# Autonoom.net
KiCad netlist of a schematic drawn in Altium Designer
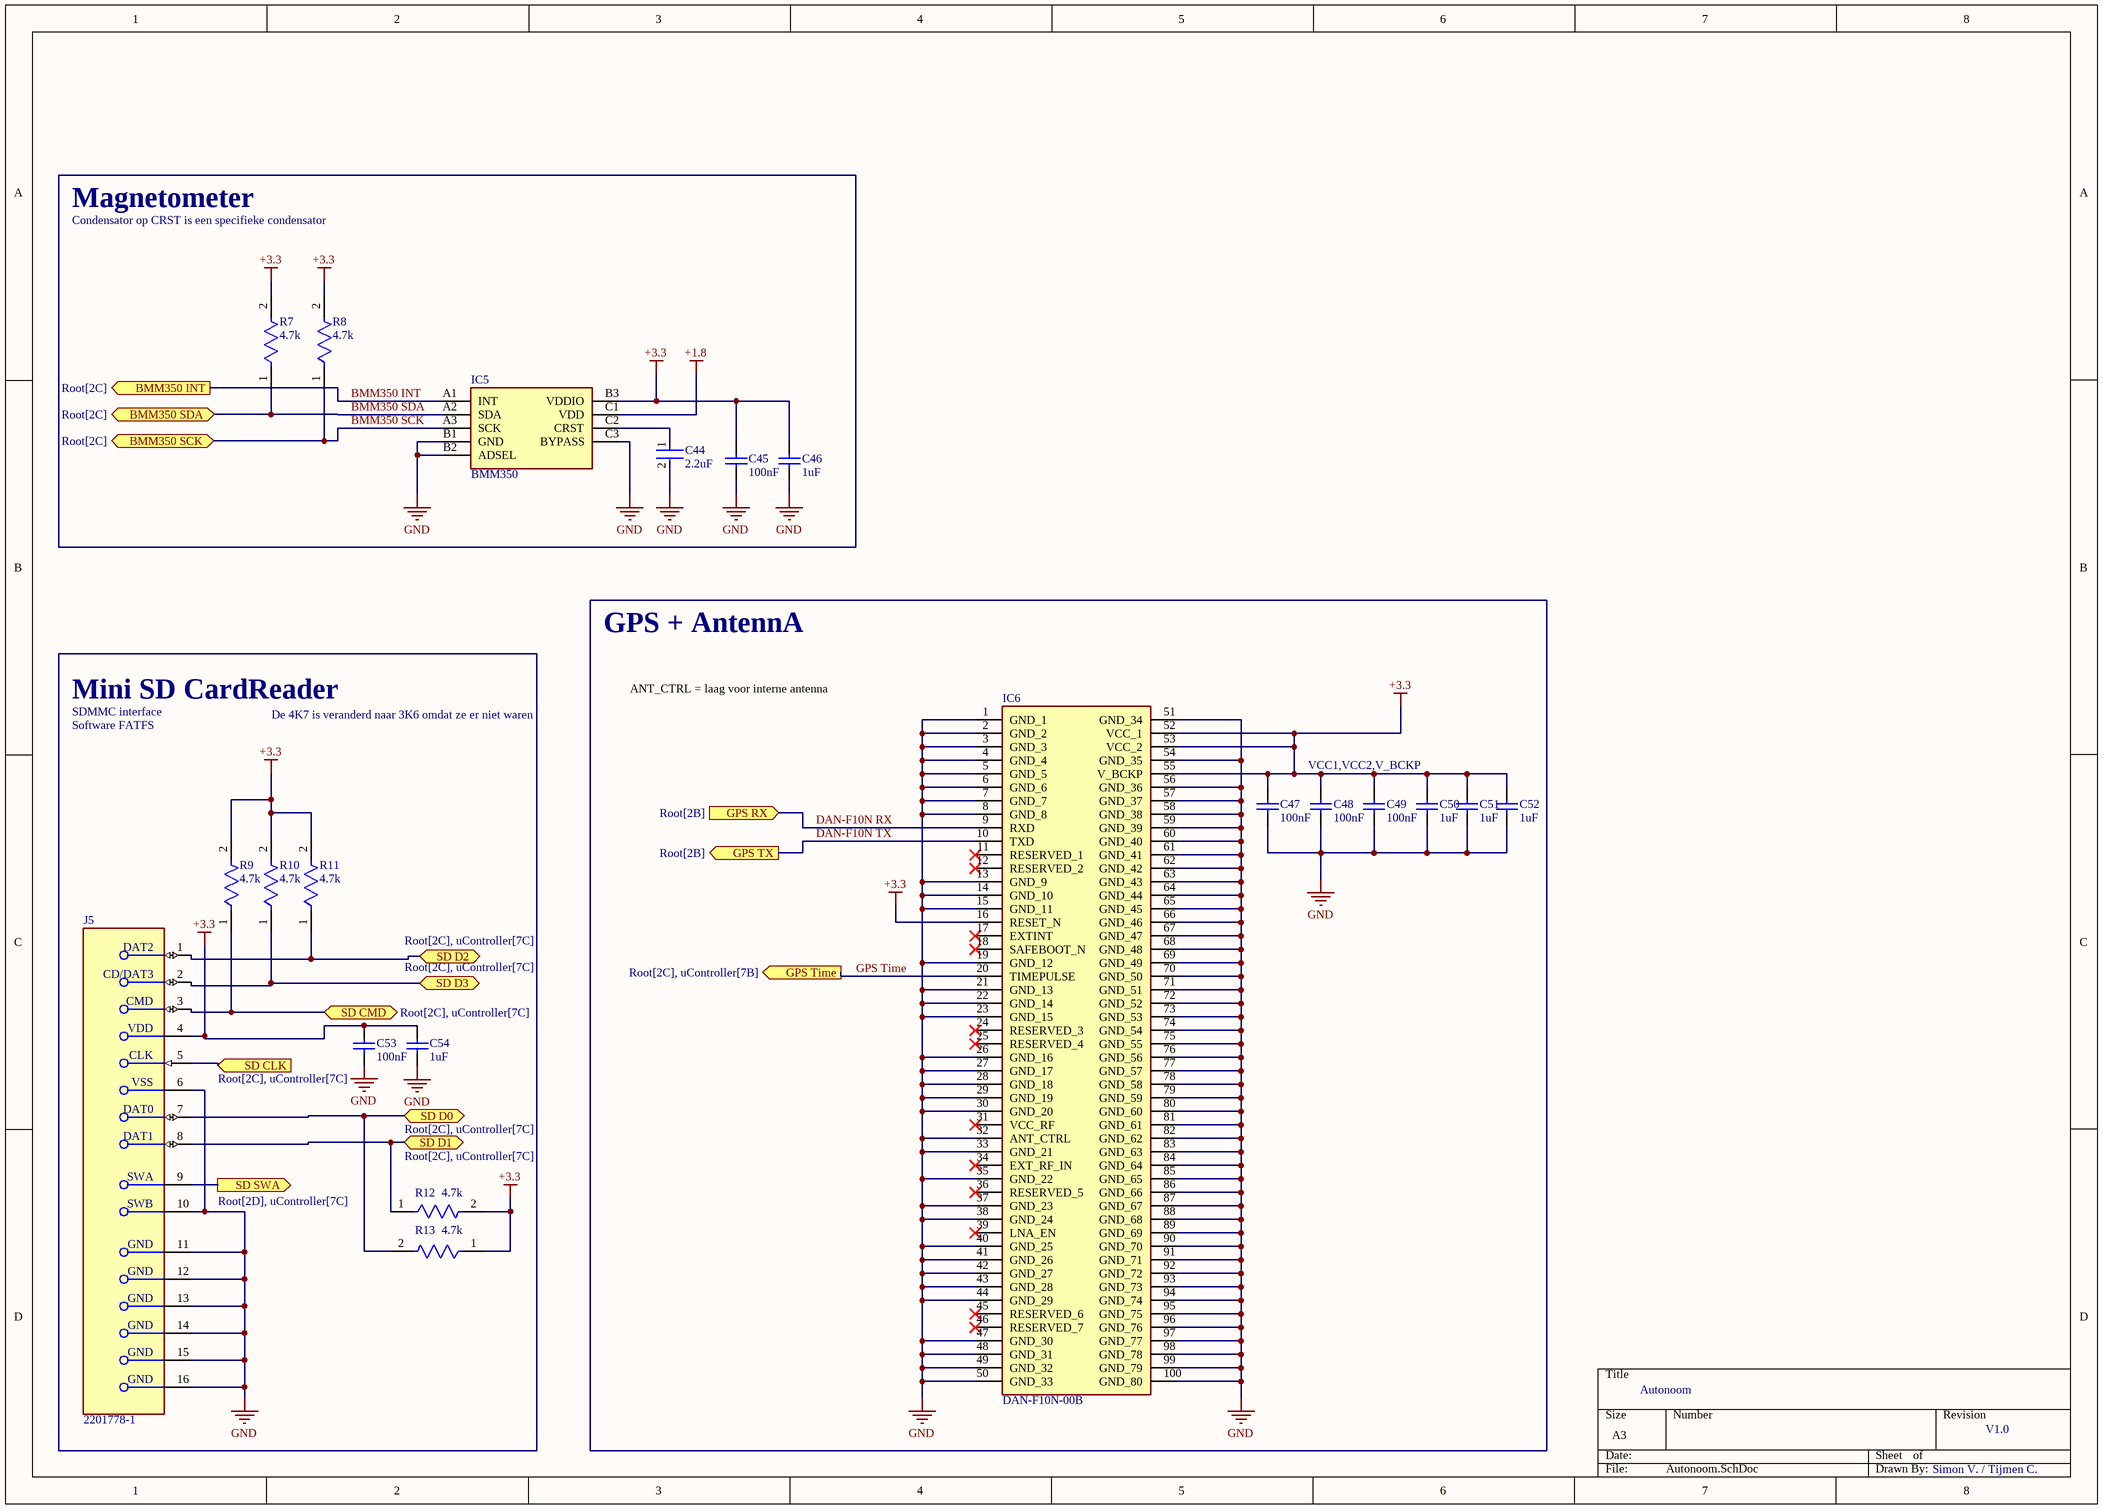
[diagram p0: Autonoom.SchDoc]

(export (version "E")
  (design (tool "Eeschema 10.0.6"))
  (components
    (comp (ref "C44")
      (value "2.2uF")
      (footprint "FP-CGB4B-MFG")
      (description "Multilayer Ceramic Capacitors 2.2uF ±10% 6.3V X7R SMD 0805, type: CGB4B3X7R0J225K055AB")
      (fields (field (name "TOLERANCE") "10%"))
      (libsource (lib "Altium Content Vault") (part "b4654b650e69147ec39a6b967a45e02"))
    )
    (comp (ref "C45")
      (value "100nF")
      (footprint "CAPC1608X92X38ML15T08")
      (fields (field (name "PART NUMBER") "VJ0603Y104MXXAC") (field (name "MANUFACTURER") "Vitramon"))
      (libsource (lib "Altium Content Vault") (part "CAP"))
    )
    (comp (ref "C46")
      (value "1uF")
      (footprint "CAPC1608X90X35NL15T15")
      (fields
        (field (name "PART NUMBER") "0603YD105MAT2A")
        (field (name "MANUFACTURER") "AVX Interconnect / Elco")
      )
      (libsource (lib "Altium Content Vault") (part "CAP"))
    )
    (comp (ref "C47")
      (value "100nF")
      (footprint "CAPC1608X92X38ML15T08")
      (fields (field (name "PART NUMBER") "VJ0603Y104MXXAC") (field (name "MANUFACTURER") "Vitramon"))
      (libsource (lib "Altium Content Vault") (part "CAP"))
    )
    (comp (ref "C48")
      (value "100nF")
      (footprint "CAPC1608X92X38ML15T08")
      (fields (field (name "PART NUMBER") "VJ0603Y104MXXAC") (field (name "MANUFACTURER") "Vitramon"))
      (libsource (lib "Altium Content Vault") (part "CAP"))
    )
    (comp (ref "C49")
      (value "100nF")
      (footprint "CAPC1608X92X38ML15T08")
      (fields (field (name "PART NUMBER") "VJ0603Y104MXXAC") (field (name "MANUFACTURER") "Vitramon"))
      (libsource (lib "Altium Content Vault") (part "CAP"))
    )
    (comp (ref "C50")
      (value "1uF")
      (footprint "CAPC1608X90X35NL15T15")
      (fields
        (field (name "PART NUMBER") "0603YD105MAT2A")
        (field (name "MANUFACTURER") "AVX Interconnect / Elco")
      )
      (libsource (lib "Altium Content Vault") (part "CAP"))
    )
    (comp (ref "C51")
      (value "1uF")
      (footprint "CAPC1608X90X35NL15T15")
      (fields
        (field (name "PART NUMBER") "0603YD105MAT2A")
        (field (name "MANUFACTURER") "AVX Interconnect / Elco")
      )
      (libsource (lib "Altium Content Vault") (part "CAP"))
    )
    (comp (ref "C52")
      (value "1uF")
      (footprint "CAPC1608X90X35NL15T15")
      (fields
        (field (name "PART NUMBER") "0603YD105MAT2A")
        (field (name "MANUFACTURER") "AVX Interconnect / Elco")
      )
      (libsource (lib "Altium Content Vault") (part "CAP"))
    )
    (comp (ref "C53")
      (value "100nF")
      (footprint "CAPC1608X92X38ML15T08")
      (fields (field (name "PART NUMBER") "VJ0603Y104MXXAC") (field (name "MANUFACTURER") "Vitramon"))
      (libsource (lib "Altium Content Vault") (part "CAP"))
    )
    (comp (ref "C54")
      (value "1uF")
      (footprint "CAPC1608X90X35NL15T15")
      (fields
        (field (name "PART NUMBER") "0603YD105MAT2A")
        (field (name "MANUFACTURER") "AVX Interconnect / Elco")
      )
      (libsource (lib "Altium Content Vault") (part "CAP"))
    )
    (comp (ref "IC5")
      (value "BMM350")
      (footprint "SamacSys:BGA9C40P3X3_128X128X54")
      (description "Integrated Circuit")
      (fields (field (name "MOUSER PART NUMBER") "262-BMM350"))
      (libsource (lib "SamacSys") (part "BMM350"))
    )
    (comp (ref "IC6")
      (value "DAN-F10N-00B")
      (footprint "SamacSys:DANF10N00B")
      (description "Integrated Circuit")
      (libsource (lib "*") (part "DAN-F10N-00B"))
    )
    (comp (ref "J5")
      (value "2201778-1")
      (footprint "FP-2201778-1-MFG")
      (description "MICRO SD PUSH PUSH LOW PROFILE T")
      (fields
        (field (name "OCTOPART") "https://octopart.com/2201778-1-te+connectivity-46448999")
        (field (name "MANUFACTURER") "TE Connectivity")
      )
      (libsource (lib "Altium Content Vault") (part "5f630df3b5079420789607a76de83c1"))
    )
    (comp (ref "R7")
      (value "4.7k")
      (footprint "FP-AC0603-IPC_A")
      (description "RES 4.7KΩ 1.00% 0.1W 0603")
      (fields (field (name "TOLERANCE") "1%"))
      (libsource (lib "Altium Content Vault") (part "1029c3af85768c4190bb7ad29bc67b5"))
    )
    (comp (ref "R8")
      (value "4.7k")
      (footprint "FP-AC0603-IPC_A")
      (description "RES 4.7KΩ 1.00% 0.1W 0603")
      (fields (field (name "TOLERANCE") "1%"))
      (libsource (lib "Altium Content Vault") (part "1029c3af85768c4190bb7ad29bc67b5"))
    )
    (comp (ref "R9")
      (value "4.7k")
      (footprint "FP-AC0603-IPC_A")
      (description "RES 4.7KΩ 1.00% 0.1W 0603")
      (fields (field (name "TOLERANCE") "1%"))
      (libsource (lib "Altium Content Vault") (part "1029c3af85768c4190bb7ad29bc67b5"))
    )
    (comp (ref "R10")
      (value "4.7k")
      (footprint "FP-AC0603-IPC_A")
      (description "RES 4.7KΩ 1.00% 0.1W 0603")
      (fields (field (name "TOLERANCE") "1%"))
      (libsource (lib "Altium Content Vault") (part "1029c3af85768c4190bb7ad29bc67b5"))
    )
    (comp (ref "R11")
      (value "4.7k")
      (footprint "FP-AC0603-IPC_A")
      (description "RES 4.7KΩ 1.00% 0.1W 0603")
      (fields (field (name "TOLERANCE") "1%"))
      (libsource (lib "Altium Content Vault") (part "1029c3af85768c4190bb7ad29bc67b5"))
    )
    (comp (ref "R12")
      (value "4.7k")
      (footprint "FP-AC0603-IPC_A")
      (description "RES 4.7KΩ 1.00% 0.1W 0603")
      (fields (field (name "TOLERANCE") "1%"))
      (libsource (lib "Altium Content Vault") (part "1029c3af85768c4190bb7ad29bc67b5"))
    )
    (comp (ref "R13")
      (value "4.7k")
      (footprint "FP-AC0603-IPC_A")
      (description "RES 4.7KΩ 1.00% 0.1W 0603")
      (fields (field (name "TOLERANCE") "1%"))
      (libsource (lib "Altium Content Vault") (part "1029c3af85768c4190bb7ad29bc67b5"))
    )
  )
  (nets
    (net (code "1") (name "+1.8") (class "Default")
      (node (ref "IC5") (pin "C1") (pinfunction "VDD_C1") (pintype "passive"))
    )
    (net (code "2") (name "+3.3") (class "Default")
      (node (ref "C45") (pin "2") (pinfunction "2_2") (pintype "passive"))
      (node (ref "C46") (pin "2") (pinfunction "2_2") (pintype "passive"))
      (node (ref "C47") (pin "2") (pinfunction "2_2") (pintype "passive"))
      (node (ref "C48") (pin "2") (pinfunction "2_2") (pintype "passive"))
      (node (ref "C49") (pin "2") (pinfunction "2_2") (pintype "passive"))
      (node (ref "C50") (pin "2") (pinfunction "2_2") (pintype "passive"))
      (node (ref "C51") (pin "2") (pinfunction "2_2") (pintype "passive"))
      (node (ref "C52") (pin "2") (pinfunction "2_2") (pintype "passive"))
      (node (ref "C53") (pin "2") (pinfunction "2_2") (pintype "passive"))
      (node (ref "C54") (pin "2") (pinfunction "2_2") (pintype "passive"))
      (node (ref "IC5") (pin "B3") (pinfunction "VDDIO_B3") (pintype "passive"))
      (node (ref "IC6") (pin "16") (pinfunction "RESET_N_16") (pintype "passive"))
      (node (ref "IC6") (pin "52") (pinfunction "VCC_1_52") (pintype "passive"))
      (node (ref "IC6") (pin "53") (pinfunction "VCC_2_53") (pintype "passive"))
      (node (ref "IC6") (pin "55") (pinfunction "V_BCKP_55") (pintype "passive"))
      (node (ref "J5") (pin "4") (pinfunction "VDD_4") (pintype "power_in"))
      (node (ref "R10") (pin "2") (pinfunction "2_2") (pintype "passive"))
      (node (ref "R11") (pin "2") (pinfunction "2_2") (pintype "passive"))
      (node (ref "R12") (pin "2") (pinfunction "2_2") (pintype "passive"))
      (node (ref "R13") (pin "1") (pinfunction "1_1") (pintype "passive"))
      (node (ref "R7") (pin "2") (pinfunction "2_2") (pintype "passive"))
      (node (ref "R8") (pin "2") (pinfunction "2_2") (pintype "passive"))
      (node (ref "R9") (pin "2") (pinfunction "2_2") (pintype "passive"))
    )
    (net (code "3") (name "/BMM350 INT") (class "Default")
      (node (ref "IC5") (pin "A1") (pinfunction "INT_A1") (pintype "passive"))
    )
    (net (code "4") (name "/BMM350 SCK") (class "Default")
      (node (ref "IC5") (pin "A3") (pinfunction "SCK_A3") (pintype "passive"))
      (node (ref "R8") (pin "1") (pinfunction "1_1") (pintype "passive"))
    )
    (net (code "5") (name "/BMM350 SDA") (class "Default")
      (node (ref "IC5") (pin "A2") (pinfunction "SDA_A2") (pintype "passive"))
      (node (ref "R7") (pin "1") (pinfunction "1_1") (pintype "passive"))
    )
    (net (code "6") (name "/DAN-F10N RX") (class "Default")
      (node (ref "IC6") (pin "9") (pinfunction "RXD_9") (pintype "passive"))
    )
    (net (code "7") (name "/DAN-F10N TX") (class "Default")
      (node (ref "IC6") (pin "10") (pinfunction "TXD_10") (pintype "passive"))
    )
    (net (code "8") (name "/GPS Time") (class "Default")
      (node (ref "IC6") (pin "20") (pinfunction "TIMEPULSE_20") (pintype "passive"))
    )
    (net (code "9") (name "/SD CLK") (class "Default")
      (node (ref "J5") (pin "5") (pinfunction "CLK_5") (pintype "input"))
    )
    (net (code "10") (name "/SD CMD") (class "Default")
      (node (ref "J5") (pin "3") (pinfunction "CMD_3") (pintype "bidirectional"))
      (node (ref "R9") (pin "1") (pinfunction "1_1") (pintype "passive"))
    )
    (net (code "11") (name "/SD D0") (class "Default")
      (node (ref "J5") (pin "7") (pinfunction "DAT0_7") (pintype "bidirectional"))
      (node (ref "R13") (pin "2") (pinfunction "2_2") (pintype "passive"))
    )
    (net (code "12") (name "/SD D1") (class "Default")
      (node (ref "J5") (pin "8") (pinfunction "DAT1_8") (pintype "bidirectional"))
      (node (ref "R12") (pin "1") (pinfunction "1_1") (pintype "passive"))
    )
    (net (code "13") (name "/SD D2") (class "Default")
      (node (ref "J5") (pin "1") (pinfunction "DAT2_1") (pintype "bidirectional"))
      (node (ref "R11") (pin "1") (pinfunction "1_1") (pintype "passive"))
    )
    (net (code "14") (name "/SD D3") (class "Default")
      (node (ref "J5") (pin "2") (pinfunction "CD/DAT3_2") (pintype "bidirectional"))
      (node (ref "R10") (pin "1") (pinfunction "1_1") (pintype "passive"))
    )
    (net (code "15") (name "/SD SWA") (class "Default")
      (node (ref "J5") (pin "9") (pinfunction "SWA_9") (pintype "passive"))
    )
    (net (code "16") (name "GND") (class "Default")
      (node (ref "C44") (pin "2") (pinfunction "2_2") (pintype "passive"))
      (node (ref "C45") (pin "1") (pinfunction "1_1") (pintype "passive"))
      (node (ref "C46") (pin "1") (pinfunction "1_1") (pintype "passive"))
      (node (ref "C47") (pin "1") (pinfunction "1_1") (pintype "passive"))
      (node (ref "C48") (pin "1") (pinfunction "1_1") (pintype "passive"))
      (node (ref "C49") (pin "1") (pinfunction "1_1") (pintype "passive"))
      (node (ref "C50") (pin "1") (pinfunction "1_1") (pintype "passive"))
      (node (ref "C51") (pin "1") (pinfunction "1_1") (pintype "passive"))
      (node (ref "C52") (pin "1") (pinfunction "1_1") (pintype "passive"))
      (node (ref "C53") (pin "1") (pinfunction "1_1") (pintype "passive"))
      (node (ref "C54") (pin "1") (pinfunction "1_1") (pintype "passive"))
      (node (ref "IC5") (pin "B1") (pinfunction "GND_B1") (pintype "passive"))
      (node (ref "IC5") (pin "B2") (pinfunction "ADSEL_B2") (pintype "passive"))
      (node (ref "IC5") (pin "C3") (pinfunction "BYPASS_C3") (pintype "passive"))
      (node (ref "IC6") (pin "1") (pinfunction "GND_1_1") (pintype "passive"))
      (node (ref "IC6") (pin "100") (pinfunction "GND_80_100") (pintype "passive"))
      (node (ref "IC6") (pin "13") (pinfunction "GND_9_13") (pintype "passive"))
      (node (ref "IC6") (pin "14") (pinfunction "GND_10_14") (pintype "passive"))
      (node (ref "IC6") (pin "15") (pinfunction "GND_11_15") (pintype "passive"))
      (node (ref "IC6") (pin "19") (pinfunction "GND_12_19") (pintype "passive"))
      (node (ref "IC6") (pin "2") (pinfunction "GND_2_2") (pintype "passive"))
      (node (ref "IC6") (pin "21") (pinfunction "GND_13_21") (pintype "passive"))
      (node (ref "IC6") (pin "22") (pinfunction "GND_14_22") (pintype "passive"))
      (node (ref "IC6") (pin "23") (pinfunction "GND_15_23") (pintype "passive"))
      (node (ref "IC6") (pin "26") (pinfunction "GND_16_26") (pintype "passive"))
      (node (ref "IC6") (pin "27") (pinfunction "GND_17_27") (pintype "passive"))
      (node (ref "IC6") (pin "28") (pinfunction "GND_18_28") (pintype "passive"))
      (node (ref "IC6") (pin "29") (pinfunction "GND_19_29") (pintype "passive"))
      (node (ref "IC6") (pin "3") (pinfunction "GND_3_3") (pintype "passive"))
      (node (ref "IC6") (pin "30") (pinfunction "GND_20_30") (pintype "passive"))
      (node (ref "IC6") (pin "32") (pinfunction "ANT_CTRL_32") (pintype "passive"))
      (node (ref "IC6") (pin "33") (pinfunction "GND_21_33") (pintype "passive"))
      (node (ref "IC6") (pin "35") (pinfunction "GND_22_35") (pintype "passive"))
      (node (ref "IC6") (pin "37") (pinfunction "GND_23_37") (pintype "passive"))
      (node (ref "IC6") (pin "38") (pinfunction "GND_24_38") (pintype "passive"))
      (node (ref "IC6") (pin "4") (pinfunction "GND_4_4") (pintype "passive"))
      (node (ref "IC6") (pin "40") (pinfunction "GND_25_40") (pintype "passive"))
      (node (ref "IC6") (pin "41") (pinfunction "GND_26_41") (pintype "passive"))
      (node (ref "IC6") (pin "42") (pinfunction "GND_27_42") (pintype "passive"))
      (node (ref "IC6") (pin "43") (pinfunction "GND_28_43") (pintype "passive"))
      (node (ref "IC6") (pin "44") (pinfunction "GND_29_44") (pintype "passive"))
      (node (ref "IC6") (pin "47") (pinfunction "GND_30_47") (pintype "passive"))
      (node (ref "IC6") (pin "48") (pinfunction "GND_31_48") (pintype "passive"))
      (node (ref "IC6") (pin "49") (pinfunction "GND_32_49") (pintype "passive"))
      (node (ref "IC6") (pin "5") (pinfunction "GND_5_5") (pintype "passive"))
      (node (ref "IC6") (pin "50") (pinfunction "GND_33_50") (pintype "passive"))
      (node (ref "IC6") (pin "51") (pinfunction "GND_34_51") (pintype "passive"))
      (node (ref "IC6") (pin "54") (pinfunction "GND_35_54") (pintype "passive"))
      (node (ref "IC6") (pin "56") (pinfunction "GND_36_56") (pintype "passive"))
      (node (ref "IC6") (pin "57") (pinfunction "GND_37_57") (pintype "passive"))
      (node (ref "IC6") (pin "58") (pinfunction "GND_38_58") (pintype "passive"))
      (node (ref "IC6") (pin "59") (pinfunction "GND_39_59") (pintype "passive"))
      (node (ref "IC6") (pin "6") (pinfunction "GND_6_6") (pintype "passive"))
      (node (ref "IC6") (pin "60") (pinfunction "GND_40_60") (pintype "passive"))
      (node (ref "IC6") (pin "61") (pinfunction "GND_41_61") (pintype "passive"))
      (node (ref "IC6") (pin "62") (pinfunction "GND_42_62") (pintype "passive"))
      (node (ref "IC6") (pin "63") (pinfunction "GND_43_63") (pintype "passive"))
      (node (ref "IC6") (pin "64") (pinfunction "GND_44_64") (pintype "passive"))
      (node (ref "IC6") (pin "65") (pinfunction "GND_45_65") (pintype "passive"))
      (node (ref "IC6") (pin "66") (pinfunction "GND_46_66") (pintype "passive"))
      (node (ref "IC6") (pin "67") (pinfunction "GND_47_67") (pintype "passive"))
      (node (ref "IC6") (pin "68") (pinfunction "GND_48_68") (pintype "passive"))
      (node (ref "IC6") (pin "69") (pinfunction "GND_49_69") (pintype "passive"))
      (node (ref "IC6") (pin "7") (pinfunction "GND_7_7") (pintype "passive"))
      (node (ref "IC6") (pin "70") (pinfunction "GND_50_70") (pintype "passive"))
      (node (ref "IC6") (pin "71") (pinfunction "GND_51_71") (pintype "passive"))
      (node (ref "IC6") (pin "72") (pinfunction "GND_52_72") (pintype "passive"))
      (node (ref "IC6") (pin "73") (pinfunction "GND_53_73") (pintype "passive"))
      (node (ref "IC6") (pin "74") (pinfunction "GND_54_74") (pintype "passive"))
      (node (ref "IC6") (pin "75") (pinfunction "GND_55_75") (pintype "passive"))
      (node (ref "IC6") (pin "76") (pinfunction "GND_56_76") (pintype "passive"))
      (node (ref "IC6") (pin "77") (pinfunction "GND_57_77") (pintype "passive"))
      (node (ref "IC6") (pin "78") (pinfunction "GND_58_78") (pintype "passive"))
      (node (ref "IC6") (pin "79") (pinfunction "GND_59_79") (pintype "passive"))
      (node (ref "IC6") (pin "8") (pinfunction "GND_8_8") (pintype "passive"))
      (node (ref "IC6") (pin "80") (pinfunction "GND_60_80") (pintype "passive"))
      (node (ref "IC6") (pin "81") (pinfunction "GND_61_81") (pintype "passive"))
      (node (ref "IC6") (pin "82") (pinfunction "GND_62_82") (pintype "passive"))
      (node (ref "IC6") (pin "83") (pinfunction "GND_63_83") (pintype "passive"))
      (node (ref "IC6") (pin "84") (pinfunction "GND_64_84") (pintype "passive"))
      (node (ref "IC6") (pin "85") (pinfunction "GND_65_85") (pintype "passive"))
      (node (ref "IC6") (pin "86") (pinfunction "GND_66_86") (pintype "passive"))
      (node (ref "IC6") (pin "87") (pinfunction "GND_67_87") (pintype "passive"))
      (node (ref "IC6") (pin "88") (pinfunction "GND_68_88") (pintype "passive"))
      (node (ref "IC6") (pin "89") (pinfunction "GND_69_89") (pintype "passive"))
      (node (ref "IC6") (pin "90") (pinfunction "GND_70_90") (pintype "passive"))
      (node (ref "IC6") (pin "91") (pinfunction "GND_71_91") (pintype "passive"))
      (node (ref "IC6") (pin "92") (pinfunction "GND_72_92") (pintype "passive"))
      (node (ref "IC6") (pin "93") (pinfunction "GND_73_93") (pintype "passive"))
      (node (ref "IC6") (pin "94") (pinfunction "GND_74_94") (pintype "passive"))
      (node (ref "IC6") (pin "95") (pinfunction "GND_75_95") (pintype "passive"))
      (node (ref "IC6") (pin "96") (pinfunction "GND_76_96") (pintype "passive"))
      (node (ref "IC6") (pin "97") (pinfunction "GND_77_97") (pintype "passive"))
      (node (ref "IC6") (pin "98") (pinfunction "GND_78_98") (pintype "passive"))
      (node (ref "IC6") (pin "99") (pinfunction "GND_79_99") (pintype "passive"))
      (node (ref "J5") (pin "10") (pinfunction "SWB_10") (pintype "passive"))
      (node (ref "J5") (pin "11") (pinfunction "GND_11") (pintype "power_in"))
      (node (ref "J5") (pin "12") (pinfunction "GND_12") (pintype "power_in"))
      (node (ref "J5") (pin "13") (pinfunction "GND_13") (pintype "power_in"))
      (node (ref "J5") (pin "14") (pinfunction "GND_14") (pintype "power_in"))
      (node (ref "J5") (pin "15") (pinfunction "GND_15") (pintype "power_in"))
      (node (ref "J5") (pin "16") (pinfunction "GND_16") (pintype "power_in"))
      (node (ref "J5") (pin "6") (pinfunction "VSS_6") (pintype "power_in"))
    )
    (net (code "17") (name "Net-(IC5-CRST)") (class "Default")
      (node (ref "C44") (pin "1") (pinfunction "1_1") (pintype "passive"))
      (node (ref "IC5") (pin "C2") (pinfunction "CRST_C2") (pintype "passive"))
    )
    (net (code "18") (name "unconnected-(IC6-EXTINT-Pad17)") (class "Default")
      (node (ref "IC6") (pin "17") (pinfunction "EXTINT_17") (pintype "passive+no_connect"))
    )
    (net (code "19") (name "unconnected-(IC6-EXT_RF_IN-Pad34)") (class "Default")
      (node (ref "IC6") (pin "34") (pinfunction "EXT_RF_IN_34") (pintype "passive+no_connect"))
    )
    (net (code "20") (name "unconnected-(IC6-LNA_EN-Pad39)") (class "Default")
      (node (ref "IC6") (pin "39") (pinfunction "LNA_EN_39") (pintype "passive+no_connect"))
    )
    (net (code "21") (name "unconnected-(IC6-RESERVED_1-Pad11)") (class "Default")
      (node (ref "IC6") (pin "11") (pinfunction "RESERVED_1_11") (pintype "passive+no_connect"))
    )
    (net (code "22") (name "unconnected-(IC6-RESERVED_2-Pad12)") (class "Default")
      (node (ref "IC6") (pin "12") (pinfunction "RESERVED_2_12") (pintype "passive+no_connect"))
    )
    (net (code "23") (name "unconnected-(IC6-RESERVED_3-Pad24)") (class "Default")
      (node (ref "IC6") (pin "24") (pinfunction "RESERVED_3_24") (pintype "passive+no_connect"))
    )
    (net (code "24") (name "unconnected-(IC6-RESERVED_4-Pad25)") (class "Default")
      (node (ref "IC6") (pin "25") (pinfunction "RESERVED_4_25") (pintype "passive+no_connect"))
    )
    (net (code "25") (name "unconnected-(IC6-RESERVED_5-Pad36)") (class "Default")
      (node (ref "IC6") (pin "36") (pinfunction "RESERVED_5_36") (pintype "passive+no_connect"))
    )
    (net (code "26") (name "unconnected-(IC6-RESERVED_6-Pad45)") (class "Default")
      (node (ref "IC6") (pin "45") (pinfunction "RESERVED_6_45") (pintype "passive+no_connect"))
    )
    (net (code "27") (name "unconnected-(IC6-RESERVED_7-Pad46)") (class "Default")
      (node (ref "IC6") (pin "46") (pinfunction "RESERVED_7_46") (pintype "passive+no_connect"))
    )
    (net (code "28") (name "unconnected-(IC6-SAFEBOOT_N-Pad18)") (class "Default")
      (node (ref "IC6") (pin "18") (pinfunction "SAFEBOOT_N_18") (pintype "passive+no_connect"))
    )
    (net (code "29") (name "unconnected-(IC6-VCC_RF-Pad31)") (class "Default")
      (node (ref "IC6") (pin "31") (pinfunction "VCC_RF_31") (pintype "passive+no_connect"))
    )
  )
)
